# Periph.net
KiCad netlist of a schematic drawn in Altium Designer
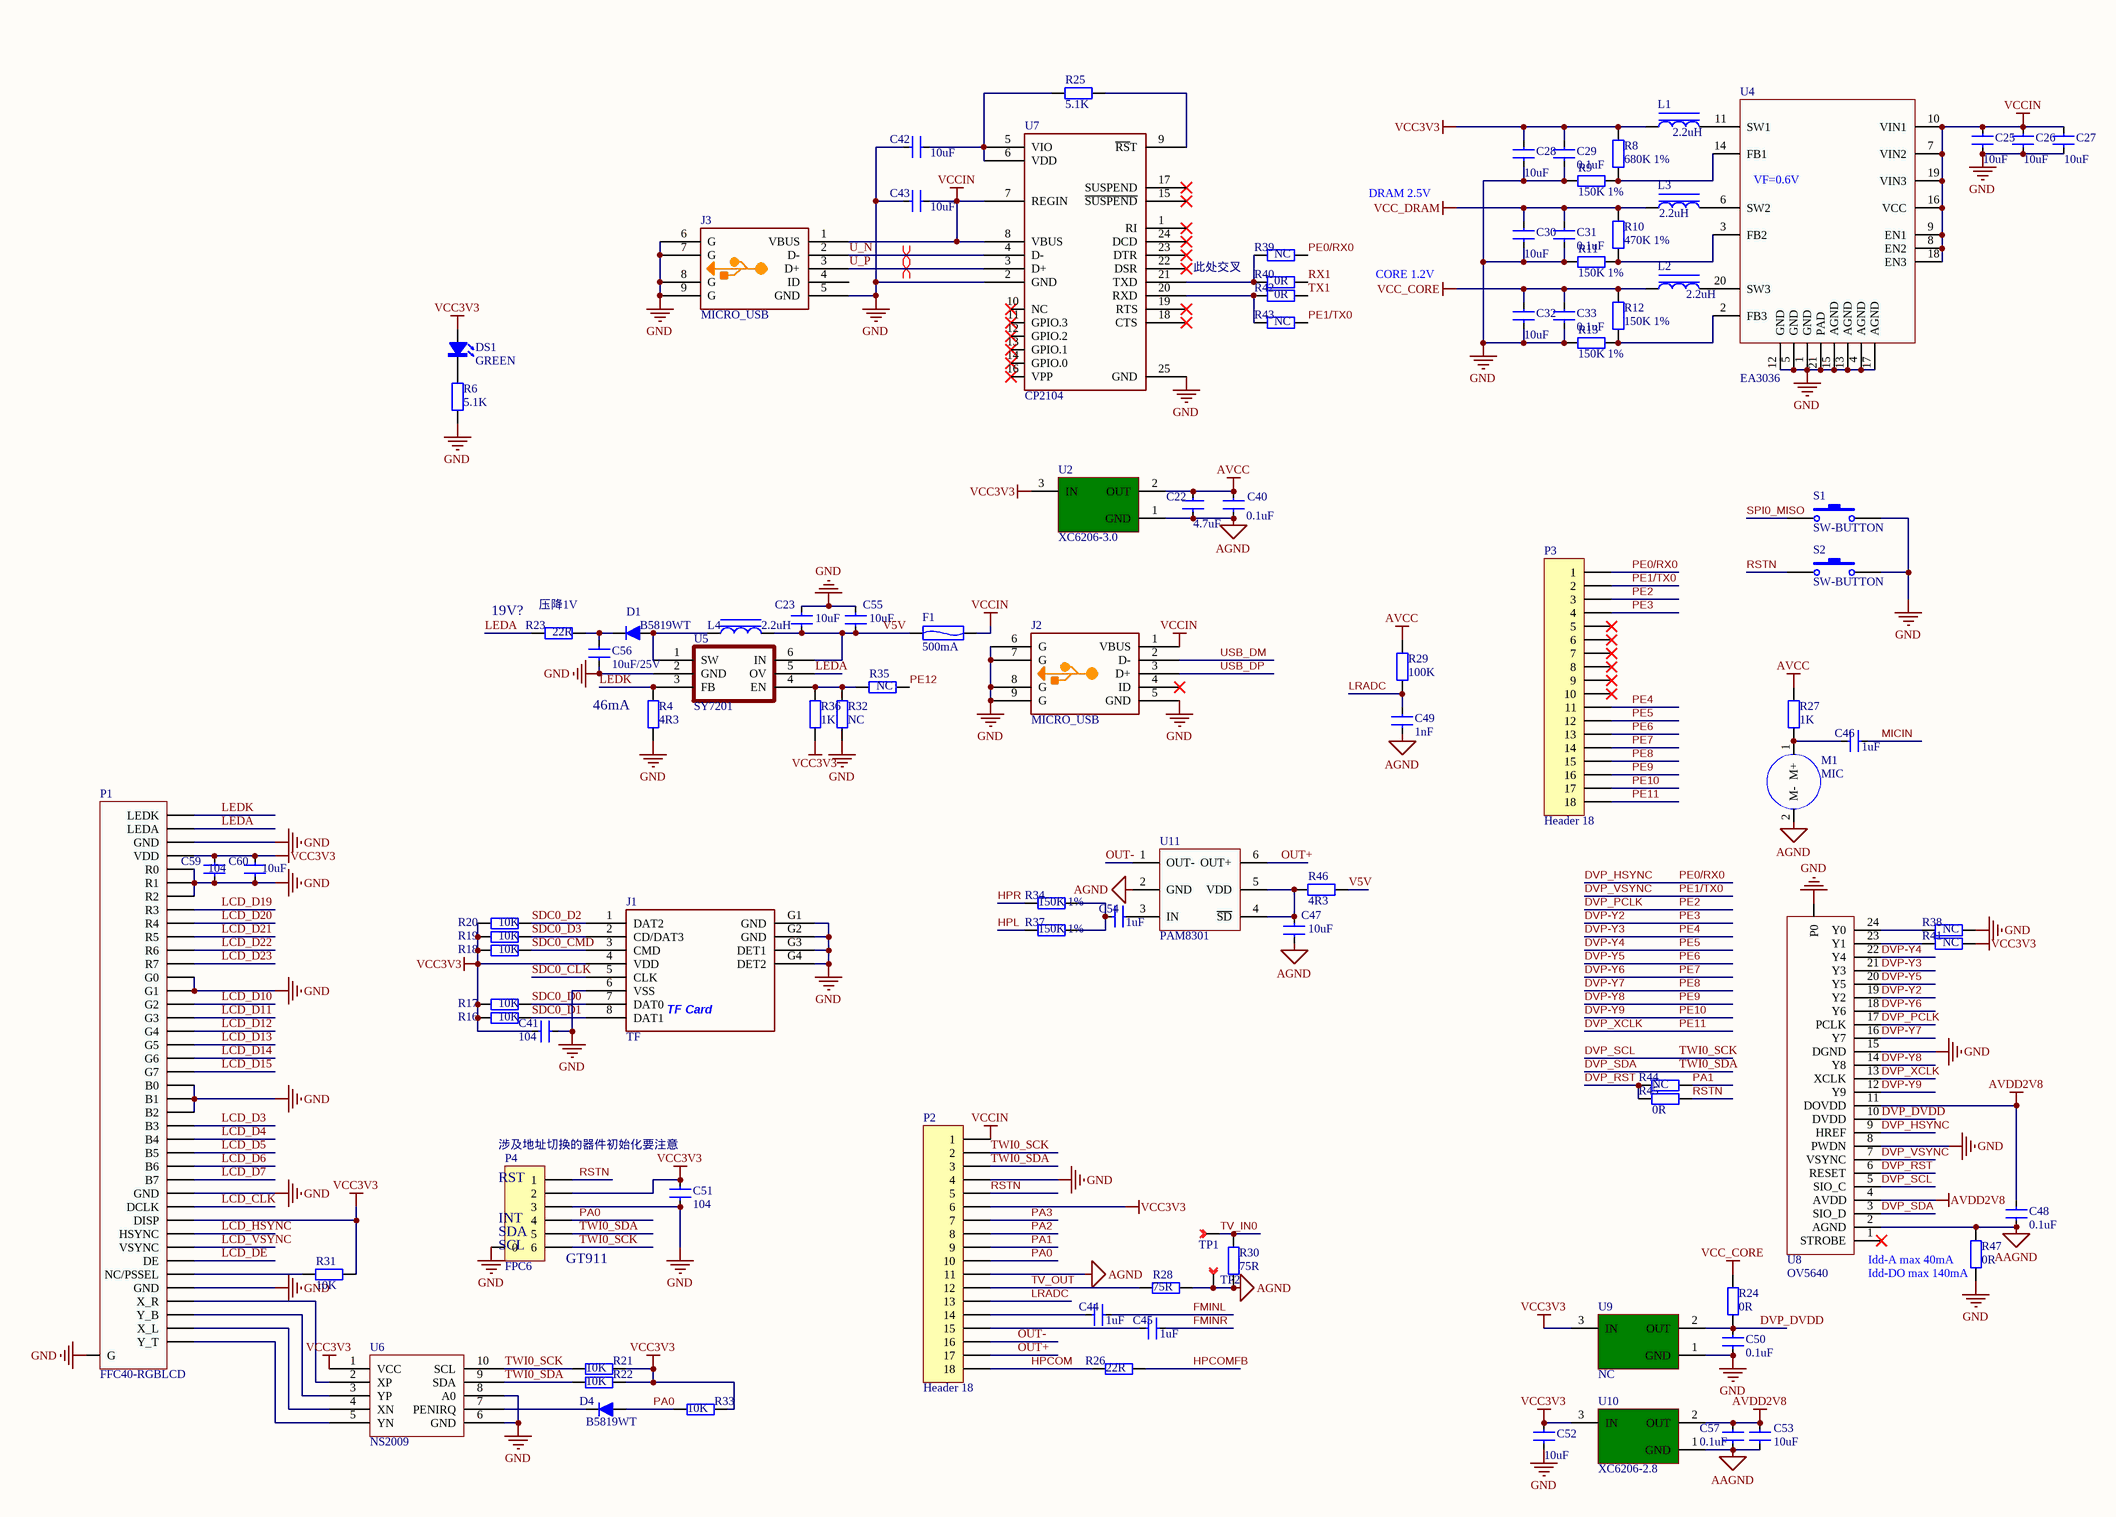
[diagram p0: Periph.SchDoc]

(export (version "E")
  (design (tool "Eeschema 10.0.6"))
  (components
    (comp (ref "C22")
      (value "4.7uF")
      (footprint "C0402")
      (description "普通小电容")
      (libsource (lib "LIB_MANGO") (part "CAP"))
    )
    (comp (ref "C23")
      (value "10uF")
      (footprint "C0402")
      (description "普通小电容")
      (libsource (lib "LIB_MANGO") (part "CAP"))
    )
    (comp (ref "C25")
      (value "10uF")
      (footprint "C0402")
      (description "普通小电容")
      (libsource (lib "LIB_MANGO") (part "CAP"))
    )
    (comp (ref "C26")
      (value "10uF")
      (footprint "C0402")
      (description "普通小电容")
      (libsource (lib "LIB_MANGO") (part "CAP"))
    )
    (comp (ref "C27")
      (value "10uF")
      (footprint "C0402")
      (description "普通小电容")
      (libsource (lib "LIB_MANGO") (part "CAP"))
    )
    (comp (ref "C28")
      (value "10uF")
      (footprint "C0402")
      (description "普通小电容")
      (libsource (lib "LIB_MANGO") (part "CAP"))
    )
    (comp (ref "C29")
      (value "0.1uF")
      (footprint "C0402")
      (description "普通小电容")
      (libsource (lib "LIB_MANGO") (part "CAP"))
    )
    (comp (ref "C30")
      (value "10uF")
      (footprint "C0402")
      (description "普通小电容")
      (libsource (lib "LIB_MANGO") (part "CAP"))
    )
    (comp (ref "C31")
      (value "0.1uF")
      (footprint "C0402")
      (description "普通小电容")
      (libsource (lib "LIB_MANGO") (part "CAP"))
    )
    (comp (ref "C32")
      (value "10uF")
      (footprint "C0402")
      (description "普通小电容")
      (libsource (lib "LIB_MANGO") (part "CAP"))
    )
    (comp (ref "C33")
      (value "0.1uF")
      (footprint "C0402")
      (description "普通小电容")
      (libsource (lib "LIB_MANGO") (part "CAP"))
    )
    (comp (ref "C40")
      (value "0.1uF")
      (footprint "C0402")
      (description "普通小电容")
      (libsource (lib "LIB_MANGO") (part "CAP"))
    )
    (comp (ref "C41")
      (value "104")
      (footprint "C0402")
      (description "普通小电容")
      (libsource (lib "LIB_MANGO") (part "CAP"))
    )
    (comp (ref "C42")
      (value "10uF")
      (footprint "C0402")
      (description "普通小电容")
      (libsource (lib "LIB_MANGO") (part "CAP"))
    )
    (comp (ref "C43")
      (value "10uF")
      (footprint "C0402")
      (description "普通小电容")
      (libsource (lib "LIB_MANGO") (part "CAP"))
    )
    (comp (ref "C44")
      (value "1uF")
      (footprint "C0402")
      (description "普通小电容")
      (libsource (lib "LIB_MANGO") (part "CAP"))
    )
    (comp (ref "C45")
      (value "1uF")
      (footprint "C0402")
      (description "普通小电容")
      (libsource (lib "LIB_MANGO") (part "CAP"))
    )
    (comp (ref "C46")
      (value "1uF")
      (footprint "C0402")
      (description "普通小电容")
      (libsource (lib "LIB_MANGO") (part "CAP"))
    )
    (comp (ref "C47")
      (value "10uF")
      (footprint "C0402")
      (description "普通小电容")
      (libsource (lib "LIB_MANGO") (part "CAP"))
    )
    (comp (ref "C48")
      (value "0.1uF")
      (footprint "C0402")
      (description "普通小电容")
      (libsource (lib "LIB_MANGO") (part "CAP"))
    )
    (comp (ref "C49")
      (value "1nF")
      (footprint "C0402")
      (description "普通小电容")
      (libsource (lib "LIB_MANGO") (part "CAP"))
    )
    (comp (ref "C50")
      (value "0.1uF")
      (footprint "C0402")
      (description "普通小电容")
      (libsource (lib "LIB_MANGO") (part "CAP"))
    )
    (comp (ref "C51")
      (value "104")
      (footprint "C0402")
      (description "普通小电容")
      (libsource (lib "LIB_MANGO") (part "CAP"))
    )
    (comp (ref "C52")
      (value "10uF")
      (footprint "C0402")
      (description "普通小电容")
      (libsource (lib "LIB_MANGO") (part "CAP"))
    )
    (comp (ref "C53")
      (value "10uF")
      (footprint "C0402")
      (description "普通小电容")
      (libsource (lib "LIB_MANGO") (part "CAP"))
    )
    (comp (ref "C54")
      (value "1uF")
      (footprint "C0402")
      (description "普通小电容")
      (libsource (lib "LIB_MANGO") (part "CAP"))
    )
    (comp (ref "C55")
      (value "10uF")
      (footprint "C0402")
      (description "普通小电容")
      (libsource (lib "LIB_MANGO") (part "CAP"))
    )
    (comp (ref "C56")
      (value "10uF/25V")
      (footprint "C0603")
      (description "普通小电容")
      (libsource (lib "LIB_MANGO") (part "CAP"))
    )
    (comp (ref "C57")
      (value "0.1uF")
      (footprint "C0402")
      (description "普通小电容")
      (libsource (lib "LIB_MANGO") (part "CAP"))
    )
    (comp (ref "C59")
      (value "104")
      (footprint "C0402")
      (description "普通小电容")
      (libsource (lib "LIB_MANGO") (part "CAP"))
    )
    (comp (ref "C60")
      (value "10uF")
      (footprint "C0402")
      (description "普通小电容")
      (libsource (lib "LIB_MANGO") (part "CAP"))
    )
    (comp (ref "D1")
      (value "B5819WT")
      (footprint "SOD523")
      (description "普通二极管")
      (libsource (lib "A") (part "Diode"))
    )
    (comp (ref "D4")
      (value "B5819WT")
      (footprint "SOD523")
      (description "普通二极管")
      (libsource (lib "A") (part "Diode"))
    )
    (comp (ref "DS1") (value "GREEN") (footprint "LED0402") (libsource (lib "A") (part "LED")))
    (comp (ref "F1") (value "500mA") (footprint "0805F") (libsource (lib "LIB_MANGO") (part "FUSE")))
    (comp (ref "J1")
      (value "TF")
      (footprint "TFCARD473092651")
      (libsource (lib "LIB_MANGO") (part "TF_473092651"))
    )
    (comp (ref "J2")
      (value "MICRO_USB")
      (footprint "MICROUSB-youxin")
      (libsource (lib "A") (part "MICRO_USB"))
    )
    (comp (ref "J3")
      (value "MICRO_USB")
      (footprint "MICROUSB-youxin")
      (libsource (lib "A") (part "MICRO_USB"))
    )
    (comp (ref "L1")
      (value "2.2uH")
      (footprint "VLS2016")
      (description "普通电感")
      (libsource (lib "LIB_MANGO") (part "L"))
    )
    (comp (ref "L2")
      (value "2.2uH")
      (footprint "VLS2016")
      (description "普通电感")
      (libsource (lib "LIB_MANGO") (part "L"))
    )
    (comp (ref "L3")
      (value "2.2uH")
      (footprint "VLS2016")
      (description "普通电感")
      (libsource (lib "A") (part "L"))
    )
    (comp (ref "L4")
      (value "2.2uH")
      (footprint "VLS3012E")
      (description "普通电感")
      (libsource (lib "LIB_MANGO") (part "L"))
    )
    (comp (ref "M1") (value "MIC") (footprint "MIC") (libsource (lib "LIB_MANGO") (part "MIC")))
    (comp (ref "P1")
      (value "FFC40-RGBLCD")
      (footprint "FFC/SM0.5-1H40")
      (fields (field (name "PUBLISHER") "Altium Limited"))
      (libsource (lib "LIB_MANGO") (part "FFC40-RGBLCD"))
    )
    (comp (ref "P2")
      (value "Header 18")
      (footprint "HDR1X18-M2")
      (description "Header, 18-Pin")
      (fields (field (name "PUBLISHER") "Altium Limited"))
      (libsource (lib "LIB_MANGO") (part "Header 18"))
    )
    (comp (ref "P3")
      (value "Header 18")
      (footprint "HDR1X18-M2")
      (description "Header, 18-Pin")
      (fields (field (name "PUBLISHER") "Altium Limited"))
      (libsource (lib "LIB_MANGO") (part "Header 18"))
    )
    (comp (ref "P4")
      (value "FPC6")
      (footprint "FPC6")
      (fields (field (name "PUBLISHER") "Altium Limited"))
      (libsource (lib "LIB_MANGO") (part "FPC6"))
    )
    (comp (ref "R4")
      (value "4R3")
      (footprint "R0402")
      (description "普通电阻")
      (libsource (lib "") (part "RES_1"))
    )
    (comp (ref "R6")
      (value "5.1K")
      (footprint "R0402")
      (description "普通电阻1%精度")
      (libsource (lib "") (part "RES_2"))
    )
    (comp (ref "R8")
      (value "680K 1%")
      (footprint "R0402")
      (description "普通电阻")
      (libsource (lib "") (part "RES_2"))
    )
    (comp (ref "R9")
      (value "150K 1%")
      (footprint "R0402")
      (description "普通电阻")
      (libsource (lib "LIB_MANGO") (part "RES"))
    )
    (comp (ref "R10")
      (value "470K 1%")
      (footprint "R0402")
      (description "普通电阻")
      (libsource (lib "") (part "RES_2"))
    )
    (comp (ref "R11")
      (value "150K 1%")
      (footprint "R0402")
      (description "普通电阻")
      (libsource (lib "LIB_MANGO") (part "RES"))
    )
    (comp (ref "R12")
      (value "150K 1%")
      (footprint "R0402")
      (description "普通电阻")
      (libsource (lib "") (part "RES_2"))
    )
    (comp (ref "R13")
      (value "150K 1%")
      (footprint "R0402")
      (description "普通电阻")
      (libsource (lib "LIB_MANGO") (part "RES"))
    )
    (comp (ref "R16")
      (value "10K")
      (footprint "R0402")
      (description "普通电阻")
      (libsource (lib "") (part "RES_1"))
    )
    (comp (ref "R17")
      (value "10K")
      (footprint "R0402")
      (description "普通电阻")
      (libsource (lib "") (part "RES_1"))
    )
    (comp (ref "R18")
      (value "10K")
      (footprint "R0402")
      (description "普通电阻")
      (libsource (lib "") (part "RES_1"))
    )
    (comp (ref "R19")
      (value "10K")
      (footprint "R0402")
      (description "普通电阻")
      (libsource (lib "") (part "RES_1"))
    )
    (comp (ref "R20")
      (value "10K")
      (footprint "R0402")
      (description "普通电阻")
      (libsource (lib "") (part "RES_1"))
    )
    (comp (ref "R21")
      (value "10K")
      (footprint "R0402")
      (description "普通电阻")
      (libsource (lib "") (part "RES_3"))
    )
    (comp (ref "R22")
      (value "10K")
      (footprint "R0402")
      (description "普通电阻")
      (libsource (lib "") (part "RES_3"))
    )
    (comp (ref "R23")
      (value "22R")
      (footprint "R0603")
      (description "普通电阻")
      (libsource (lib "LIB_MANGO") (part "RES"))
    )
    (comp (ref "R24")
      (value "0R")
      (footprint "R0402")
      (description "普通电阻")
      (libsource (lib "") (part "RES_1"))
    )
    (comp (ref "R25")
      (value "5.1K")
      (footprint "R0402")
      (description "普通电阻")
      (libsource (lib "") (part "RES_3"))
    )
    (comp (ref "R26")
      (value "22R")
      (footprint "R0402")
      (description "普通电阻")
      (libsource (lib "") (part "RES_3"))
    )
    (comp (ref "R27")
      (value "1K")
      (footprint "R0402")
      (description "普通电阻")
      (libsource (lib "") (part "RES_2"))
    )
    (comp (ref "R28")
      (value "75R")
      (footprint "R0402")
      (description "普通电阻")
      (libsource (lib "") (part "RES_3"))
    )
    (comp (ref "R29")
      (value "100K")
      (footprint "R0402")
      (description "普通电阻")
      (libsource (lib "") (part "RES_1"))
    )
    (comp (ref "R30")
      (value "75R")
      (footprint "R0402")
      (description "普通电阻")
      (libsource (lib "") (part "RES_2"))
    )
    (comp (ref "R31")
      (value "10K")
      (footprint "R0402")
      (description "普通电阻")
      (libsource (lib "LIB_MANGO") (part "RES"))
    )
    (comp (ref "R32")
      (value "NC")
      (footprint "R0402")
      (description "普通电阻")
      (libsource (lib "") (part "RES_2"))
    )
    (comp (ref "R33")
      (value "10K")
      (footprint "R0402")
      (description "普通电阻")
      (libsource (lib "") (part "RES_3"))
    )
    (comp (ref "R34")
      (value "150K 1%")
      (footprint "R0402")
      (description "普通电阻")
      (libsource (lib "LIB_MANGO") (part "RES"))
    )
    (comp (ref "R35")
      (value "NC")
      (footprint "R0402")
      (description "普通电阻")
      (libsource (lib "") (part "RES_3"))
    )
    (comp (ref "R36")
      (value "1K")
      (footprint "R0402")
      (description "普通电阻")
      (libsource (lib "") (part "RES_1"))
    )
    (comp (ref "R37")
      (value "150K 1%")
      (footprint "R0402")
      (description "普通电阻")
      (libsource (lib "LIB_MANGO") (part "RES"))
    )
    (comp (ref "R38")
      (value "NC")
      (footprint "R0402")
      (description "普通电阻")
      (libsource (lib "") (part "RES_3"))
    )
    (comp (ref "R39")
      (value "NC")
      (footprint "R0402")
      (description "普通电阻")
      (libsource (lib "LIB_MANGO") (part "RES"))
    )
    (comp (ref "R40")
      (value "0R")
      (footprint "R0402")
      (description "普通电阻")
      (libsource (lib "LIB_MANGO") (part "RES"))
    )
    (comp (ref "R41")
      (value "NC")
      (footprint "R0402")
      (description "普通电阻")
      (libsource (lib "") (part "RES_3"))
    )
    (comp (ref "R42")
      (value "0R")
      (footprint "R0402")
      (description "普通电阻")
      (libsource (lib "LIB_MANGO") (part "RES"))
    )
    (comp (ref "R43")
      (value "NC")
      (footprint "R0402")
      (description "普通电阻")
      (libsource (lib "LIB_MANGO") (part "RES"))
    )
    (comp (ref "R44")
      (value "NC")
      (footprint "R0402")
      (description "普通电阻")
      (libsource (lib "LIB_MANGO") (part "RES"))
    )
    (comp (ref "R45")
      (value "0R")
      (footprint "R0402")
      (description "普通电阻")
      (libsource (lib "") (part "RES_3"))
    )
    (comp (ref "R46")
      (value "4R3")
      (footprint "R0402")
      (description "普通电阻")
      (libsource (lib "LIB_MANGO") (part "RES"))
    )
    (comp (ref "R47")
      (value "0R")
      (footprint "R0402")
      (description "普通电阻")
      (libsource (lib "") (part "RES_2"))
    )
    (comp (ref "S1")
      (value "SW-BUTTON")
      (footprint "MINIBUTTON")
      (libsource (lib "LIB_MANGO") (part "SW-BUTTON"))
    )
    (comp (ref "S2")
      (value "SW-BUTTON")
      (footprint "MINIBUTTON")
      (libsource (lib "LIB_MANGO") (part "SW-BUTTON"))
    )
    (comp (ref "TP1")
      (value "TEST POINT")
      (footprint "TEST-POINT")
      (description "Description")
      (libsource (lib "LIB_MANGO") (part "TP"))
    )
    (comp (ref "TP2")
      (value "TEST POINT")
      (footprint "TEST-POINT")
      (description "Description")
      (libsource (lib "LIB_MANGO") (part "TP"))
    )
    (comp (ref "U2") (value "XC6206-3.0") (footprint "SOT23") (libsource (lib "LIB_MANGO") (part "XC6206")))
    (comp (ref "U4")
      (value "EA3036")
      (footprint "QFN40P300X300X80_HS-21N")
      (libsource (lib "LIB_MANGO") (part "EA3036"))
    )
    (comp (ref "U5") (value "SY7201") (footprint "SOT23-6") (libsource (lib "LIB_MANGO") (part "PT4101")))
    (comp (ref "U6") (value "NS2009") (footprint "TSSOP10") (libsource (lib "LIB_MANGO") (part "NS2009")))
    (comp (ref "U7") (value "CP2104") (footprint "QFN24") (libsource (lib "LIB_MANGO") (part "CP2104")))
    (comp (ref "U8")
      (value "OV5640")
      (footprint "FFC/SM0.5-1H24 - OV2640")
      (description "Header, 24-Pin")
      (fields (field (name "PUBLISHER") "Altium Limited"))
      (libsource (lib "A") (part "OV5640"))
    )
    (comp (ref "U9") (value "NC") (footprint "SOT23") (libsource (lib "LIB_MANGO") (part "XC6206")))
    (comp (ref "U10") (value "XC6206-2.8") (footprint "SOT23") (libsource (lib "LIB_MANGO") (part "XC6206")))
    (comp (ref "U11") (value "PAM8301") (footprint "SOT23-6") (libsource (lib "LIB_MANGO") (part "PAM8301")))
  )
  (nets
    (net (code "1") (name "/DVP-Y2") (class "Default")
      (node (ref "P3") (pin "4") (pinfunction "4_4") (pintype "passive"))
      (node (ref "U8") (pin "19") (pinfunction "Y2_19") (pintype "passive"))
    )
    (net (code "2") (name "/DVP-Y3") (class "Default")
      (node (ref "P3") (pin "11") (pinfunction "11_11") (pintype "passive"))
      (node (ref "U8") (pin "21") (pinfunction "Y3_21") (pintype "passive"))
    )
    (net (code "3") (name "/DVP-Y4") (class "Default")
      (node (ref "P3") (pin "12") (pinfunction "12_12") (pintype "passive"))
      (node (ref "U8") (pin "22") (pinfunction "Y4_22") (pintype "passive"))
    )
    (net (code "4") (name "/DVP-Y5") (class "Default")
      (node (ref "P3") (pin "13") (pinfunction "13_13") (pintype "passive"))
      (node (ref "U8") (pin "20") (pinfunction "Y5_20") (pintype "passive"))
    )
    (net (code "5") (name "/DVP-Y6") (class "Default")
      (node (ref "P3") (pin "14") (pinfunction "14_14") (pintype "passive"))
      (node (ref "U8") (pin "18") (pinfunction "Y6_18") (pintype "passive"))
    )
    (net (code "6") (name "/DVP-Y7") (class "Default")
      (node (ref "P3") (pin "15") (pinfunction "15_15") (pintype "passive"))
      (node (ref "U8") (pin "16") (pinfunction "Y7_16") (pintype "passive"))
    )
    (net (code "7") (name "/DVP-Y8") (class "Default")
      (node (ref "P3") (pin "16") (pinfunction "16_16") (pintype "passive"))
      (node (ref "U8") (pin "14") (pinfunction "Y8_14") (pintype "passive"))
    )
    (net (code "8") (name "/DVP-Y9") (class "Default")
      (node (ref "P3") (pin "17") (pinfunction "17_17") (pintype "passive"))
      (node (ref "U8") (pin "12") (pinfunction "Y9_12") (pintype "passive"))
    )
    (net (code "9") (name "/DVP_DVDD") (class "Default")
      (node (ref "C50") (pin "2") (pinfunction "2_2") (pintype "passive"))
      (node (ref "R24") (pin "1") (pinfunction "1_1") (pintype "passive"))
      (node (ref "U8") (pin "10") (pinfunction "DVDD_10") (pintype "passive"))
      (node (ref "U9") (pin "2") (pinfunction "OUT_2") (pintype "passive"))
    )
    (net (code "10") (name "/DVP_HSYNC") (class "Default")
      (node (ref "P3") (pin "1") (pinfunction "1_1") (pintype "passive"))
      (node (ref "R39") (pin "1") (pinfunction "1_1") (pintype "passive"))
      (node (ref "U8") (pin "9") (pinfunction "HREF_9") (pintype "passive"))
    )
    (net (code "11") (name "/DVP_PCLK") (class "Default")
      (node (ref "P3") (pin "3") (pinfunction "3_3") (pintype "passive"))
      (node (ref "U8") (pin "17") (pinfunction "PCLK_17") (pintype "passive"))
    )
    (net (code "12") (name "/DVP_RST") (class "Default")
      (node (ref "R44") (pin "2") (pinfunction "2_2") (pintype "passive"))
      (node (ref "R45") (pin "1") (pinfunction "1_1") (pintype "passive"))
      (node (ref "U8") (pin "6") (pinfunction "RESET_6") (pintype "passive"))
    )
    (net (code "13") (name "/DVP_SCL") (class "Default")
      (node (ref "P2") (pin "2") (pinfunction "2_2") (pintype "passive"))
      (node (ref "P4") (pin "6") (pinfunction "6_6") (pintype "passive"))
      (node (ref "R21") (pin "1") (pinfunction "1_1") (pintype "passive"))
      (node (ref "U6") (pin "10") (pinfunction "SCL_10") (pintype "passive"))
      (node (ref "U8") (pin "5") (pinfunction "SIO_C_5") (pintype "passive"))
    )
    (net (code "14") (name "/DVP_SDA") (class "Default")
      (node (ref "P2") (pin "3") (pinfunction "3_3") (pintype "passive"))
      (node (ref "P4") (pin "5") (pinfunction "5_5") (pintype "passive"))
      (node (ref "R22") (pin "1") (pinfunction "1_1") (pintype "passive"))
      (node (ref "U6") (pin "9") (pinfunction "SDA_9") (pintype "passive"))
      (node (ref "U8") (pin "3") (pinfunction "SIO_D_3") (pintype "passive"))
    )
    (net (code "15") (name "/DVP_VSYNC") (class "Default")
      (node (ref "P3") (pin "2") (pinfunction "2_2") (pintype "passive"))
      (node (ref "R43") (pin "1") (pinfunction "1_1") (pintype "passive"))
      (node (ref "U8") (pin "7") (pinfunction "VSYNC_7") (pintype "passive"))
    )
    (net (code "16") (name "/DVP_XCLK") (class "Default")
      (node (ref "P3") (pin "18") (pinfunction "18_18") (pintype "passive"))
      (node (ref "U8") (pin "13") (pinfunction "XCLK_13") (pintype "passive"))
    )
    (net (code "17") (name "/FMINL") (class "Default")
      (node (ref "C44") (pin "2") (pinfunction "2_2") (pintype "passive"))
    )
    (net (code "18") (name "/FMINR") (class "Default")
      (node (ref "C45") (pin "2") (pinfunction "2_2") (pintype "passive"))
    )
    (net (code "19") (name "/HPCOM") (class "Default")
      (node (ref "P2") (pin "18") (pinfunction "18_18") (pintype "passive"))
      (node (ref "R26") (pin "1") (pinfunction "1_1") (pintype "passive"))
    )
    (net (code "20") (name "/HPCOMFB") (class "Default")
      (node (ref "R26") (pin "2") (pinfunction "2_2") (pintype "passive"))
    )
    (net (code "21") (name "/HPL") (class "Default")
      (node (ref "R37") (pin "2") (pinfunction "2_2") (pintype "passive"))
    )
    (net (code "22") (name "/HPR") (class "Default")
      (node (ref "R34") (pin "2") (pinfunction "2_2") (pintype "passive"))
    )
    (net (code "23") (name "/LCD_CLK") (class "Default")
      (node (ref "P1") (pin "30") (pinfunction "DCLK_30") (pintype "passive"))
    )
    (net (code "24") (name "/LCD_D3") (class "Default")
      (node (ref "P1") (pin "24") (pinfunction "B3_24") (pintype "passive"))
    )
    (net (code "25") (name "/LCD_D4") (class "Default")
      (node (ref "P1") (pin "25") (pinfunction "B4_25") (pintype "passive"))
    )
    (net (code "26") (name "/LCD_D5") (class "Default")
      (node (ref "P1") (pin "26") (pinfunction "B5_26") (pintype "passive"))
    )
    (net (code "27") (name "/LCD_D6") (class "Default")
      (node (ref "P1") (pin "27") (pinfunction "B6_27") (pintype "passive"))
    )
    (net (code "28") (name "/LCD_D7") (class "Default")
      (node (ref "P1") (pin "28") (pinfunction "B7_28") (pintype "passive"))
    )
    (net (code "29") (name "/LCD_D10") (class "Default")
      (node (ref "P1") (pin "15") (pinfunction "G2_15") (pintype "passive"))
    )
    (net (code "30") (name "/LCD_D11") (class "Default")
      (node (ref "P1") (pin "16") (pinfunction "G3_16") (pintype "passive"))
    )
    (net (code "31") (name "/LCD_D12") (class "Default")
      (node (ref "P1") (pin "17") (pinfunction "G4_17") (pintype "passive"))
    )
    (net (code "32") (name "/LCD_D13") (class "Default")
      (node (ref "P1") (pin "18") (pinfunction "G5_18") (pintype "passive"))
    )
    (net (code "33") (name "/LCD_D14") (class "Default")
      (node (ref "P1") (pin "19") (pinfunction "G6_19") (pintype "passive"))
    )
    (net (code "34") (name "/LCD_D15") (class "Default")
      (node (ref "P1") (pin "20") (pinfunction "G7_20") (pintype "passive"))
    )
    (net (code "35") (name "/LCD_D19") (class "Default")
      (node (ref "P1") (pin "8") (pinfunction "R3_8") (pintype "passive"))
    )
    (net (code "36") (name "/LCD_D20") (class "Default")
      (node (ref "P1") (pin "9") (pinfunction "R4_9") (pintype "passive"))
    )
    (net (code "37") (name "/LCD_D21") (class "Default")
      (node (ref "P1") (pin "10") (pinfunction "R5_10") (pintype "passive"))
    )
    (net (code "38") (name "/LCD_D22") (class "Default")
      (node (ref "P1") (pin "11") (pinfunction "R6_11") (pintype "passive"))
    )
    (net (code "39") (name "/LCD_D23") (class "Default")
      (node (ref "P1") (pin "12") (pinfunction "R7_12") (pintype "passive"))
    )
    (net (code "40") (name "/LCD_DE") (class "Default")
      (node (ref "P1") (pin "34") (pinfunction "DE_34") (pintype "passive"))
    )
    (net (code "41") (name "/LCD_HSYNC") (class "Default")
      (node (ref "P1") (pin "32") (pinfunction "HSYNC_32") (pintype "passive"))
    )
    (net (code "42") (name "/LCD_VSYNC") (class "Default")
      (node (ref "P1") (pin "33") (pinfunction "VSYNC_33") (pintype "passive"))
    )
    (net (code "43") (name "/LEDA") (class "Default")
      (node (ref "P1") (pin "2") (pinfunction "LEDA_2") (pintype "passive"))
      (node (ref "R23") (pin "2") (pinfunction "2_2") (pintype "passive"))
      (node (ref "U5") (pin "5") (pinfunction "OV_5") (pintype "passive"))
    )
    (net (code "44") (name "/LEDK") (class "Default")
      (node (ref "P1") (pin "1") (pinfunction "LEDK_1") (pintype "passive"))
      (node (ref "R4") (pin "2") (pinfunction "2_2") (pintype "passive"))
      (node (ref "U5") (pin "3") (pinfunction "FB_3") (pintype "passive"))
    )
    (net (code "45") (name "/LRADC") (class "Default")
      (node (ref "C49") (pin "2") (pinfunction "2_2") (pintype "passive"))
      (node (ref "P2") (pin "13") (pinfunction "13_13") (pintype "passive"))
      (node (ref "R29") (pin "1") (pinfunction "1_1") (pintype "passive"))
    )
    (net (code "46") (name "/MICIN") (class "Default")
      (node (ref "C46") (pin "2") (pinfunction "2_2") (pintype "passive"))
    )
    (net (code "47") (name "/OUT+") (class "Default")
      (node (ref "P2") (pin "17") (pinfunction "17_17") (pintype "passive"))
      (node (ref "U11") (pin "6") (pinfunction "OUT+_6") (pintype "passive"))
    )
    (net (code "48") (name "/OUT-") (class "Default")
      (node (ref "P2") (pin "16") (pinfunction "16_16") (pintype "passive"))
      (node (ref "U11") (pin "1") (pinfunction "OUT-_1") (pintype "passive"))
    )
    (net (code "49") (name "/PA0") (class "Default")
      (node (ref "D4") (pin "A") (pinfunction "A_A") (pintype "passive"))
      (node (ref "P2") (pin "10") (pinfunction "10_10") (pintype "passive"))
      (node (ref "P4") (pin "4") (pinfunction "4_4") (pintype "passive"))
      (node (ref "R33") (pin "1") (pinfunction "1_1") (pintype "passive"))
    )
    (net (code "50") (name "/PA1") (class "Default")
      (node (ref "P2") (pin "9") (pinfunction "9_9") (pintype "passive"))
      (node (ref "R44") (pin "1") (pinfunction "1_1") (pintype "passive"))
    )
    (net (code "51") (name "/PA2") (class "Default")
      (node (ref "P2") (pin "8") (pinfunction "8_8") (pintype "passive"))
    )
    (net (code "52") (name "/PA3") (class "Default")
      (node (ref "P2") (pin "7") (pinfunction "7_7") (pintype "passive"))
    )
    (net (code "53") (name "/PE12") (class "Default")
      (node (ref "R35") (pin "2") (pinfunction "2_2") (pintype "passive"))
    )
    (net (code "54") (name "/RSTN") (class "Default")
      (node (ref "P2") (pin "5") (pinfunction "5_5") (pintype "passive"))
      (node (ref "P4") (pin "1") (pinfunction "1_1") (pintype "passive"))
      (node (ref "R45") (pin "2") (pinfunction "2_2") (pintype "passive"))
      (node (ref "S2") (pin "1") (pinfunction "1_1") (pintype "passive"))
    )
    (net (code "55") (name "/RX1") (class "Default")
      (node (ref "R40") (pin "1") (pinfunction "1_1") (pintype "passive"))
    )
    (net (code "56") (name "/SDC0_CLK") (class "Default")
      (node (ref "J1") (pin "5") (pinfunction "CLK_5") (pintype "passive"))
    )
    (net (code "57") (name "/SDC0_CMD") (class "Default")
      (node (ref "J1") (pin "3") (pinfunction "CMD_3") (pintype "passive"))
      (node (ref "R18") (pin "2") (pinfunction "2_2") (pintype "passive"))
    )
    (net (code "58") (name "/SDC0_D0") (class "Default")
      (node (ref "J1") (pin "7") (pinfunction "DAT0_7") (pintype "passive"))
      (node (ref "R17") (pin "2") (pinfunction "2_2") (pintype "passive"))
    )
    (net (code "59") (name "/SDC0_D1") (class "Default")
      (node (ref "J1") (pin "8") (pinfunction "DAT1_8") (pintype "passive"))
      (node (ref "R16") (pin "2") (pinfunction "2_2") (pintype "passive"))
    )
    (net (code "60") (name "/SDC0_D2") (class "Default")
      (node (ref "J1") (pin "1") (pinfunction "DAT2_1") (pintype "passive"))
      (node (ref "R20") (pin "2") (pinfunction "2_2") (pintype "passive"))
    )
    (net (code "61") (name "/SDC0_D3") (class "Default")
      (node (ref "J1") (pin "2") (pinfunction "CD/DAT3_2") (pintype "passive"))
      (node (ref "R19") (pin "2") (pinfunction "2_2") (pintype "passive"))
    )
    (net (code "62") (name "/SPI0_MISO") (class "Default")
      (node (ref "S1") (pin "1") (pinfunction "1_1") (pintype "passive"))
    )
    (net (code "63") (name "/TV_IN0") (class "Default")
      (node (ref "R30") (pin "1") (pinfunction "1_1") (pintype "passive"))
      (node (ref "TP1") (pin "1") (pinfunction "1_1") (pintype "passive"))
    )
    (net (code "64") (name "/TV_OUT") (class "Default")
      (node (ref "P2") (pin "12") (pinfunction "12_12") (pintype "passive"))
      (node (ref "R28") (pin "1") (pinfunction "1_1") (pintype "passive"))
    )
    (net (code "65") (name "/TX1") (class "Default")
      (node (ref "R42") (pin "1") (pinfunction "1_1") (pintype "passive"))
    )
    (net (code "66") (name "/USB_DM") (class "Default")
      (node (ref "J2") (pin "2") (pinfunction "D-_2") (pintype "passive"))
    )
    (net (code "67") (name "/USB_DP") (class "Default")
      (node (ref "J2") (pin "3") (pinfunction "D+_3") (pintype "passive"))
    )
    (net (code "68") (name "/U_N") (class "Default")
      (node (ref "J3") (pin "2") (pinfunction "D-_2") (pintype "passive"))
      (node (ref "U7") (pin "4") (pinfunction "D-_4") (pintype "passive"))
    )
    (net (code "69") (name "/U_P") (class "Default")
      (node (ref "J3") (pin "3") (pinfunction "D+_3") (pintype "passive"))
      (node (ref "U7") (pin "3") (pinfunction "D+_3") (pintype "passive"))
    )
    (net (code "70") (name "/V5V") (class "Default")
      (node (ref "C23") (pin "1") (pinfunction "1_1") (pintype "passive"))
      (node (ref "C55") (pin "2") (pinfunction "2_2") (pintype "passive"))
      (node (ref "F1") (pin "1") (pinfunction "1_1") (pintype "passive"))
      (node (ref "L4") (pin "1") (pinfunction "1_1") (pintype "passive"))
      (node (ref "R46") (pin "1") (pinfunction "1_1") (pintype "passive"))
      (node (ref "U5") (pin "6") (pinfunction "IN_6") (pintype "passive"))
    )
    (net (code "71") (name "AAGND") (class "Default")
      (node (ref "C48") (pin "1") (pinfunction "1_1") (pintype "passive"))
      (node (ref "C53") (pin "2") (pinfunction "2_2") (pintype "passive"))
      (node (ref "C57") (pin "1") (pinfunction "1_1") (pintype "passive"))
      (node (ref "R47") (pin "1") (pinfunction "1_1") (pintype "passive"))
      (node (ref "U10") (pin "1") (pinfunction "GND_1") (pintype "passive"))
      (node (ref "U8") (pin "2") (pinfunction "AGND_2") (pintype "passive"))
    )
    (net (code "72") (name "AGND") (class "Default")
      (node (ref "C22") (pin "1") (pinfunction "1_1") (pintype "passive"))
      (node (ref "C40") (pin "1") (pinfunction "1_1") (pintype "passive"))
      (node (ref "C47") (pin "2") (pinfunction "2_2") (pintype "passive"))
      (node (ref "C49") (pin "1") (pinfunction "1_1") (pintype "passive"))
      (node (ref "M1") (pin "2") (pinfunction "M-_2") (pintype "passive"))
      (node (ref "P2") (pin "11") (pinfunction "11_11") (pintype "passive"))
      (node (ref "R28") (pin "2") (pinfunction "2_2") (pintype "passive"))
      (node (ref "R30") (pin "2") (pinfunction "2_2") (pintype "passive"))
      (node (ref "TP2") (pin "1") (pinfunction "1_1") (pintype "passive"))
      (node (ref "U11") (pin "2") (pinfunction "GND_2") (pintype "passive"))
      (node (ref "U2") (pin "1") (pinfunction "GND_1") (pintype "passive"))
    )
    (net (code "73") (name "AVCC") (class "Default")
      (node (ref "C22") (pin "2") (pinfunction "2_2") (pintype "passive"))
      (node (ref "C40") (pin "2") (pinfunction "2_2") (pintype "passive"))
      (node (ref "R27") (pin "1") (pinfunction "1_1") (pintype "passive"))
      (node (ref "R29") (pin "2") (pinfunction "2_2") (pintype "passive"))
      (node (ref "U2") (pin "2") (pinfunction "OUT_2") (pintype "passive"))
    )
    (net (code "74") (name "AVDD2V8") (class "Default")
      (node (ref "C48") (pin "2") (pinfunction "2_2") (pintype "passive"))
      (node (ref "C53") (pin "1") (pinfunction "1_1") (pintype "passive"))
      (node (ref "C57") (pin "2") (pinfunction "2_2") (pintype "passive"))
      (node (ref "U10") (pin "2") (pinfunction "OUT_2") (pintype "passive"))
      (node (ref "U8") (pin "11") (pinfunction "DOVDD_11") (pintype "passive"))
      (node (ref "U8") (pin "4") (pinfunction "AVDD_4") (pintype "passive"))
    )
    (net (code "75") (name "GND") (class "Default")
      (node (ref "C23") (pin "2") (pinfunction "2_2") (pintype "passive"))
      (node (ref "C25") (pin "2") (pinfunction "2_2") (pintype "passive"))
      (node (ref "C26") (pin "2") (pinfunction "2_2") (pintype "passive"))
      (node (ref "C27") (pin "2") (pinfunction "2_2") (pintype "passive"))
      (node (ref "C28") (pin "2") (pinfunction "2_2") (pintype "passive"))
      (node (ref "C29") (pin "1") (pinfunction "1_1") (pintype "passive"))
      (node (ref "C30") (pin "2") (pinfunction "2_2") (pintype "passive"))
      (node (ref "C31") (pin "1") (pinfunction "1_1") (pintype "passive"))
      (node (ref "C32") (pin "2") (pinfunction "2_2") (pintype "passive"))
      (node (ref "C33") (pin "1") (pinfunction "1_1") (pintype "passive"))
      (node (ref "C41") (pin "2") (pinfunction "2_2") (pintype "passive"))
      (node (ref "C42") (pin "2") (pinfunction "2_2") (pintype "passive"))
      (node (ref "C43") (pin "1") (pinfunction "1_1") (pintype "passive"))
      (node (ref "C50") (pin "1") (pinfunction "1_1") (pintype "passive"))
      (node (ref "C51") (pin "1") (pinfunction "1_1") (pintype "passive"))
      (node (ref "C52") (pin "2") (pinfunction "2_2") (pintype "passive"))
      (node (ref "C55") (pin "1") (pinfunction "1_1") (pintype "passive"))
      (node (ref "C56") (pin "1") (pinfunction "1_1") (pintype "passive"))
      (node (ref "C59") (pin "2") (pinfunction "2_2") (pintype "passive"))
      (node (ref "C60") (pin "1") (pinfunction "1_1") (pintype "passive"))
      (node (ref "J1") (pin "6") (pinfunction "VSS_6") (pintype "power_in"))
      (node (ref "J1") (pin "G1") (pinfunction "GND_G1") (pintype "power_in"))
      (node (ref "J1") (pin "G2") (pinfunction "GND_G2") (pintype "power_in"))
      (node (ref "J1") (pin "G3") (pinfunction "DET1_G3") (pintype "power_in"))
      (node (ref "J1") (pin "G4") (pinfunction "DET2_G4") (pintype "power_in"))
      (node (ref "J2") (pin "5") (pinfunction "GND_5") (pintype "power_in"))
      (node (ref "J2") (pin "6") (pinfunction "G_6") (pintype "passive"))
      (node (ref "J2") (pin "7") (pinfunction "G_7") (pintype "passive"))
      (node (ref "J2") (pin "8") (pinfunction "G_8") (pintype "passive"))
      (node (ref "J2") (pin "9") (pinfunction "G_9") (pintype "passive"))
      (node (ref "J3") (pin "5") (pinfunction "GND_5") (pintype "power_in"))
      (node (ref "J3") (pin "6") (pinfunction "G_6") (pintype "passive"))
      (node (ref "J3") (pin "7") (pinfunction "G_7") (pintype "passive"))
      (node (ref "J3") (pin "8") (pinfunction "G_8") (pintype "passive"))
      (node (ref "J3") (pin "9") (pinfunction "G_9") (pintype "passive"))
      (node (ref "P1") (pin "13") (pinfunction "G0_13") (pintype "passive"))
      (node (ref "P1") (pin "14") (pinfunction "G1_14") (pintype "passive"))
      (node (ref "P1") (pin "21") (pinfunction "B0_21") (pintype "passive"))
      (node (ref "P1") (pin "22") (pinfunction "B1_22") (pintype "passive"))
      (node (ref "P1") (pin "23") (pinfunction "B2_23") (pintype "passive"))
      (node (ref "P1") (pin "29") (pinfunction "GND_29") (pintype "passive"))
      (node (ref "P1") (pin "3") (pinfunction "GND_3") (pintype "passive"))
      (node (ref "P1") (pin "36") (pinfunction "GND_36") (pintype "passive"))
      (node (ref "P1") (pin "5") (pinfunction "R0_5") (pintype "passive"))
      (node (ref "P1") (pin "6") (pinfunction "R1_6") (pintype "passive"))
      (node (ref "P1") (pin "7") (pinfunction "R2_7") (pintype "passive"))
      (node (ref "P1") (pin "G") (pinfunction "G_G") (pintype "passive"))
      (node (ref "P2") (pin "4") (pinfunction "4_4") (pintype "passive"))
      (node (ref "P4") (pin "0") (pinfunction "0_0") (pintype "passive"))
      (node (ref "P4") (pin "3") (pinfunction "3_3") (pintype "passive"))
      (node (ref "R11") (pin "2") (pinfunction "2_2") (pintype "passive"))
      (node (ref "R13") (pin "2") (pinfunction "2_2") (pintype "passive"))
      (node (ref "R32") (pin "2") (pinfunction "2_2") (pintype "passive"))
      (node (ref "R38") (pin "2") (pinfunction "2_2") (pintype "passive"))
      (node (ref "R4") (pin "1") (pinfunction "1_1") (pintype "passive"))
      (node (ref "R47") (pin "2") (pinfunction "2_2") (pintype "passive"))
      (node (ref "R6") (pin "2") (pinfunction "2_2") (pintype "passive"))
      (node (ref "R9") (pin "2") (pinfunction "2_2") (pintype "passive"))
      (node (ref "S1") (pin "2") (pinfunction "2_2") (pintype "passive"))
      (node (ref "S2") (pin "2") (pinfunction "2_2") (pintype "passive"))
      (node (ref "U4") (pin "1") (pinfunction "GND_1") (pintype "passive"))
      (node (ref "U4") (pin "12") (pinfunction "GND_12") (pintype "passive"))
      (node (ref "U4") (pin "13") (pinfunction "AGND_13") (pintype "passive"))
      (node (ref "U4") (pin "15") (pinfunction "AGND_15") (pintype "passive"))
      (node (ref "U4") (pin "17") (pinfunction "AGND_17") (pintype "passive"))
      (node (ref "U4") (pin "21") (pinfunction "PAD_21") (pintype "passive"))
      (node (ref "U4") (pin "4") (pinfunction "AGND_4") (pintype "passive"))
      (node (ref "U4") (pin "5") (pinfunction "GND_5") (pintype "passive"))
      (node (ref "U5") (pin "2") (pinfunction "GND_2") (pintype "passive"))
      (node (ref "U6") (pin "6") (pinfunction "GND_6") (pintype "passive"))
      (node (ref "U6") (pin "8") (pinfunction "A0_8") (pintype "passive"))
      (node (ref "U7") (pin "2") (pinfunction "GND_2") (pintype "power_in"))
      (node (ref "U7") (pin "25") (pinfunction "GND_25") (pintype "power_in"))
      (node (ref "U8") (pin "15") (pinfunction "DGND_15") (pintype "passive"))
      (node (ref "U8") (pin "8") (pinfunction "PWDN_8") (pintype "passive"))
      (node (ref "U8") (pin "P0") (pinfunction "P0_P0") (pintype "passive"))
      (node (ref "U9") (pin "1") (pinfunction "GND_1") (pintype "passive"))
    )
    (net (code "76") (name "Net-(C44-Pad1)") (class "Default")
      (node (ref "C44") (pin "1") (pinfunction "1_1") (pintype "passive"))
      (node (ref "P2") (pin "14") (pinfunction "14_14") (pintype "passive"))
    )
    (net (code "77") (name "Net-(C45-Pad1)") (class "Default")
      (node (ref "C45") (pin "1") (pinfunction "1_1") (pintype "passive"))
      (node (ref "P2") (pin "15") (pinfunction "15_15") (pintype "passive"))
    )
    (net (code "78") (name "Net-(C54-Pad1)") (class "Default")
      (node (ref "C54") (pin "1") (pinfunction "1_1") (pintype "passive"))
      (node (ref "R34") (pin "1") (pinfunction "1_1") (pintype "passive"))
      (node (ref "R37") (pin "1") (pinfunction "1_1") (pintype "passive"))
    )
    (net (code "79") (name "Net-(C56-Pad2)") (class "Default")
      (node (ref "C56") (pin "2") (pinfunction "2_2") (pintype "passive"))
      (node (ref "D1") (pin "K") (pinfunction "K_K") (pintype "passive"))
      (node (ref "R23") (pin "1") (pinfunction "1_1") (pintype "passive"))
    )
    (net (code "80") (name "Net-(DS1-2)") (class "Default")
      (node (ref "DS1") (pin "K") (pinfunction "2_K") (pintype "passive"))
      (node (ref "R6") (pin "1") (pinfunction "1_1") (pintype "passive"))
    )
    (net (code "81") (name "Net-(M1-M+)") (class "Default")
      (node (ref "C46") (pin "1") (pinfunction "1_1") (pintype "passive"))
      (node (ref "M1") (pin "1") (pinfunction "M+_1") (pintype "passive"))
      (node (ref "R27") (pin "2") (pinfunction "2_2") (pintype "passive"))
    )
    (net (code "82") (name "Net-(P1-NC{slash}PSSEL)") (class "Default")
      (node (ref "P1") (pin "35") (pinfunction "NC/PSSEL_35") (pintype "passive"))
      (node (ref "R31") (pin "2") (pinfunction "2_2") (pintype "passive"))
    )
    (net (code "83") (name "Net-(P1-X_L)") (class "Default")
      (node (ref "P1") (pin "39") (pinfunction "X_L_39") (pintype "passive"))
      (node (ref "U6") (pin "4") (pinfunction "XN_4") (pintype "passive"))
    )
    (net (code "84") (name "Net-(P1-X_R)") (class "Default")
      (node (ref "P1") (pin "37") (pinfunction "X_R_37") (pintype "passive"))
      (node (ref "U6") (pin "2") (pinfunction "XP_2") (pintype "passive"))
    )
    (net (code "85") (name "Net-(P1-Y_B)") (class "Default")
      (node (ref "P1") (pin "38") (pinfunction "Y_B_38") (pintype "passive"))
      (node (ref "U6") (pin "3") (pinfunction "YP_3") (pintype "passive"))
    )
    (net (code "86") (name "Net-(P1-Y_T)") (class "Default")
      (node (ref "P1") (pin "40") (pinfunction "Y_T_40") (pintype "passive"))
      (node (ref "U6") (pin "5") (pinfunction "YN_5") (pintype "passive"))
    )
    (net (code "87") (name "Net-(U4-FB1)") (class "Default")
      (node (ref "R8") (pin "2") (pinfunction "2_2") (pintype "passive"))
      (node (ref "R9") (pin "1") (pinfunction "1_1") (pintype "passive"))
      (node (ref "U4") (pin "14") (pinfunction "FB1_14") (pintype "passive"))
    )
    (net (code "88") (name "Net-(U4-FB2)") (class "Default")
      (node (ref "R10") (pin "2") (pinfunction "2_2") (pintype "passive"))
      (node (ref "R11") (pin "1") (pinfunction "1_1") (pintype "passive"))
      (node (ref "U4") (pin "3") (pinfunction "FB2_3") (pintype "passive"))
    )
    (net (code "89") (name "Net-(U4-FB3)") (class "Default")
      (node (ref "R12") (pin "2") (pinfunction "2_2") (pintype "passive"))
      (node (ref "R13") (pin "1") (pinfunction "1_1") (pintype "passive"))
      (node (ref "U4") (pin "2") (pinfunction "FB3_2") (pintype "passive"))
    )
    (net (code "90") (name "Net-(U4-SW1)") (class "Default")
      (node (ref "L1") (pin "1") (pinfunction "1_1") (pintype "passive"))
      (node (ref "U4") (pin "11") (pinfunction "SW1_11") (pintype "passive"))
    )
    (net (code "91") (name "Net-(U4-SW2)") (class "Default")
      (node (ref "L3") (pin "1") (pinfunction "1_1") (pintype "passive"))
      (node (ref "U4") (pin "6") (pinfunction "SW2_6") (pintype "passive"))
    )
    (net (code "92") (name "Net-(U4-SW3)") (class "Default")
      (node (ref "L2") (pin "1") (pinfunction "1_1") (pintype "passive"))
      (node (ref "U4") (pin "20") (pinfunction "SW3_20") (pintype "passive"))
    )
    (net (code "93") (name "Net-(U5-EN)") (class "Default")
      (node (ref "R32") (pin "1") (pinfunction "1_1") (pintype "passive"))
      (node (ref "R35") (pin "1") (pinfunction "1_1") (pintype "passive"))
      (node (ref "R36") (pin "2") (pinfunction "2_2") (pintype "passive"))
      (node (ref "U5") (pin "4") (pinfunction "EN_4") (pintype "passive"))
    )
    (net (code "94") (name "Net-(U5-SW)") (class "Default")
      (node (ref "D1") (pin "A") (pinfunction "A_A") (pintype "passive"))
      (node (ref "L4") (pin "2") (pinfunction "2_2") (pintype "passive"))
      (node (ref "U5") (pin "1") (pinfunction "SW_1") (pintype "passive"))
    )
    (net (code "95") (name "Net-(U6-PENIRQ)") (class "Default")
      (node (ref "D4") (pin "K") (pinfunction "K_K") (pintype "passive"))
      (node (ref "U6") (pin "7") (pinfunction "PENIRQ_7") (pintype "passive"))
    )
    (net (code "96") (name "Net-(U7-RXD)") (class "Default")
      (node (ref "R42") (pin "2") (pinfunction "2_2") (pintype "passive"))
      (node (ref "R43") (pin "2") (pinfunction "2_2") (pintype "passive"))
      (node (ref "U7") (pin "20") (pinfunction "RXD_20") (pintype "passive"))
    )
    (net (code "97") (name "Net-(U7-TXD)") (class "Default")
      (node (ref "R39") (pin "2") (pinfunction "2_2") (pintype "passive"))
      (node (ref "R40") (pin "2") (pinfunction "2_2") (pintype "passive"))
      (node (ref "U7") (pin "21") (pinfunction "TXD_21") (pintype "passive"))
    )
    (net (code "98") (name "Net-(U7-VDD)") (class "Default")
      (node (ref "C42") (pin "1") (pinfunction "1_1") (pintype "passive"))
      (node (ref "R25") (pin "1") (pinfunction "1_1") (pintype "passive"))
      (node (ref "U7") (pin "5") (pinfunction "VIO_5") (pintype "passive"))
      (node (ref "U7") (pin "6") (pinfunction "VDD_6") (pintype "passive"))
    )
    (net (code "99") (name "Net-(U7-~{RS}T)") (class "Default")
      (node (ref "R25") (pin "2") (pinfunction "2_2") (pintype "passive"))
      (node (ref "U7") (pin "9") (pinfunction "~{RS}T_9") (pintype "passive"))
    )
    (net (code "100") (name "Net-(U8-Y0)") (class "Default")
      (node (ref "R38") (pin "1") (pinfunction "1_1") (pintype "passive"))
      (node (ref "U8") (pin "24") (pinfunction "Y0_24") (pintype "passive"))
    )
    (net (code "101") (name "Net-(U8-Y1)") (class "Default")
      (node (ref "R41") (pin "1") (pinfunction "1_1") (pintype "passive"))
      (node (ref "U8") (pin "23") (pinfunction "Y1_23") (pintype "passive"))
    )
    (net (code "102") (name "Net-(U11-IN)") (class "Default")
      (node (ref "C54") (pin "2") (pinfunction "2_2") (pintype "passive"))
      (node (ref "U11") (pin "3") (pinfunction "IN_3") (pintype "passive"))
    )
    (net (code "103") (name "Net-(U11-VDD)") (class "Default")
      (node (ref "C47") (pin "1") (pinfunction "1_1") (pintype "passive"))
      (node (ref "R46") (pin "2") (pinfunction "2_2") (pintype "passive"))
      (node (ref "U11") (pin "4") (pinfunction "~{SD}_4") (pintype "passive"))
      (node (ref "U11") (pin "5") (pinfunction "VDD_5") (pintype "passive"))
    )
    (net (code "104") (name "VCC3V3") (class "Default")
      (node (ref "C28") (pin "1") (pinfunction "1_1") (pintype "passive"))
      (node (ref "C29") (pin "2") (pinfunction "2_2") (pintype "passive"))
      (node (ref "C41") (pin "1") (pinfunction "1_1") (pintype "passive"))
      (node (ref "C51") (pin "2") (pinfunction "2_2") (pintype "passive"))
      (node (ref "C52") (pin "1") (pinfunction "1_1") (pintype "passive"))
      (node (ref "C59") (pin "1") (pinfunction "1_1") (pintype "passive"))
      (node (ref "C60") (pin "2") (pinfunction "2_2") (pintype "passive"))
      (node (ref "DS1") (pin "A") (pinfunction "1_A") (pintype "passive"))
      (node (ref "J1") (pin "4") (pinfunction "VDD_4") (pintype "power_in"))
      (node (ref "L1") (pin "2") (pinfunction "2_2") (pintype "passive"))
      (node (ref "P1") (pin "31") (pinfunction "DISP_31") (pintype "passive"))
      (node (ref "P1") (pin "4") (pinfunction "VDD_4") (pintype "passive"))
      (node (ref "P2") (pin "6") (pinfunction "6_6") (pintype "passive"))
      (node (ref "P4") (pin "2") (pinfunction "2_2") (pintype "passive"))
      (node (ref "R16") (pin "1") (pinfunction "1_1") (pintype "passive"))
      (node (ref "R17") (pin "1") (pinfunction "1_1") (pintype "passive"))
      (node (ref "R18") (pin "1") (pinfunction "1_1") (pintype "passive"))
      (node (ref "R19") (pin "1") (pinfunction "1_1") (pintype "passive"))
      (node (ref "R20") (pin "1") (pinfunction "1_1") (pintype "passive"))
      (node (ref "R21") (pin "2") (pinfunction "2_2") (pintype "passive"))
      (node (ref "R22") (pin "2") (pinfunction "2_2") (pintype "passive"))
      (node (ref "R31") (pin "1") (pinfunction "1_1") (pintype "passive"))
      (node (ref "R33") (pin "2") (pinfunction "2_2") (pintype "passive"))
      (node (ref "R36") (pin "1") (pinfunction "1_1") (pintype "passive"))
      (node (ref "R41") (pin "2") (pinfunction "2_2") (pintype "passive"))
      (node (ref "R8") (pin "1") (pinfunction "1_1") (pintype "passive"))
      (node (ref "U10") (pin "3") (pinfunction "IN_3") (pintype "passive"))
      (node (ref "U2") (pin "3") (pinfunction "IN_3") (pintype "passive"))
      (node (ref "U6") (pin "1") (pinfunction "VCC_1") (pintype "passive"))
      (node (ref "U9") (pin "3") (pinfunction "IN_3") (pintype "passive"))
    )
    (net (code "105") (name "VCCIN") (class "Default")
      (node (ref "C25") (pin "1") (pinfunction "1_1") (pintype "passive"))
      (node (ref "C26") (pin "1") (pinfunction "1_1") (pintype "passive"))
      (node (ref "C27") (pin "1") (pinfunction "1_1") (pintype "passive"))
      (node (ref "C43") (pin "2") (pinfunction "2_2") (pintype "passive"))
      (node (ref "F1") (pin "2") (pinfunction "2_2") (pintype "passive"))
      (node (ref "J2") (pin "1") (pinfunction "VBUS_1") (pintype "power_in"))
      (node (ref "J3") (pin "1") (pinfunction "VBUS_1") (pintype "power_in"))
      (node (ref "P2") (pin "1") (pinfunction "1_1") (pintype "passive"))
      (node (ref "U4") (pin "10") (pinfunction "VIN1_10") (pintype "passive"))
      (node (ref "U4") (pin "16") (pinfunction "VCC_16") (pintype "passive"))
      (node (ref "U4") (pin "18") (pinfunction "EN3_18") (pintype "passive"))
      (node (ref "U4") (pin "19") (pinfunction "VIN3_19") (pintype "passive"))
      (node (ref "U4") (pin "7") (pinfunction "VIN2_7") (pintype "passive"))
      (node (ref "U4") (pin "8") (pinfunction "EN2_8") (pintype "passive"))
      (node (ref "U4") (pin "9") (pinfunction "EN1_9") (pintype "passive"))
      (node (ref "U7") (pin "7") (pinfunction "REGIN_7") (pintype "passive"))
      (node (ref "U7") (pin "8") (pinfunction "VBUS_8") (pintype "power_in"))
    )
    (net (code "106") (name "VCC_CORE") (class "Default")
      (node (ref "C32") (pin "1") (pinfunction "1_1") (pintype "passive"))
      (node (ref "C33") (pin "2") (pinfunction "2_2") (pintype "passive"))
      (node (ref "L2") (pin "2") (pinfunction "2_2") (pintype "passive"))
      (node (ref "R12") (pin "1") (pinfunction "1_1") (pintype "passive"))
      (node (ref "R24") (pin "2") (pinfunction "2_2") (pintype "passive"))
    )
    (net (code "107") (name "VCC_DRAM") (class "Default")
      (node (ref "C30") (pin "1") (pinfunction "1_1") (pintype "passive"))
      (node (ref "C31") (pin "2") (pinfunction "2_2") (pintype "passive"))
      (node (ref "L3") (pin "2") (pinfunction "2_2") (pintype "passive"))
      (node (ref "R10") (pin "1") (pinfunction "1_1") (pintype "passive"))
    )
    (net (code "108") (name "unconnected-(J2-ID-Pad4)") (class "Default")
      (node (ref "J2") (pin "4") (pinfunction "ID_4") (pintype "passive+no_connect"))
    )
    (net (code "109") (name "unconnected-(J3-ID-Pad4)") (class "Default")
      (node (ref "J3") (pin "4") (pinfunction "ID_4") (pintype "passive"))
    )
    (net (code "110") (name "unconnected-(P3-Pad5)") (class "Default")
      (node (ref "P3") (pin "5") (pinfunction "5_5") (pintype "passive+no_connect"))
    )
    (net (code "111") (name "unconnected-(P3-Pad6)") (class "Default")
      (node (ref "P3") (pin "6") (pinfunction "6_6") (pintype "passive+no_connect"))
    )
    (net (code "112") (name "unconnected-(P3-Pad7)") (class "Default")
      (node (ref "P3") (pin "7") (pinfunction "7_7") (pintype "passive+no_connect"))
    )
    (net (code "113") (name "unconnected-(P3-Pad8)") (class "Default")
      (node (ref "P3") (pin "8") (pinfunction "8_8") (pintype "passive+no_connect"))
    )
    (net (code "114") (name "unconnected-(P3-Pad9)") (class "Default")
      (node (ref "P3") (pin "9") (pinfunction "9_9") (pintype "passive+no_connect"))
    )
    (net (code "115") (name "unconnected-(P3-Pad10)") (class "Default")
      (node (ref "P3") (pin "10") (pinfunction "10_10") (pintype "passive+no_connect"))
    )
    (net (code "116") (name "unconnected-(U7-CTS-Pad18)") (class "Default")
      (node (ref "U7") (pin "18") (pinfunction "CTS_18") (pintype "passive+no_connect"))
    )
    (net (code "117") (name "unconnected-(U7-DCD-Pad24)") (class "Default")
      (node (ref "U7") (pin "24") (pinfunction "DCD_24") (pintype "passive+no_connect"))
    )
    (net (code "118") (name "unconnected-(U7-DSR-Pad22)") (class "Default")
      (node (ref "U7") (pin "22") (pinfunction "DSR_22") (pintype "passive+no_connect"))
    )
    (net (code "119") (name "unconnected-(U7-DTR-Pad23)") (class "Default")
      (node (ref "U7") (pin "23") (pinfunction "DTR_23") (pintype "passive+no_connect"))
    )
    (net (code "120") (name "unconnected-(U7-GPIO.0-Pad14)") (class "Default")
      (node (ref "U7") (pin "14") (pinfunction "GPIO.0_14") (pintype "passive+no_connect"))
    )
    (net (code "121") (name "unconnected-(U7-GPIO.1-Pad13)") (class "Default")
      (node (ref "U7") (pin "13") (pinfunction "GPIO.1_13") (pintype "passive+no_connect"))
    )
    (net (code "122") (name "unconnected-(U7-GPIO.2-Pad12)") (class "Default")
      (node (ref "U7") (pin "12") (pinfunction "GPIO.2_12") (pintype "passive+no_connect"))
    )
    (net (code "123") (name "unconnected-(U7-GPIO.3-Pad11)") (class "Default")
      (node (ref "U7") (pin "11") (pinfunction "GPIO.3_11") (pintype "passive+no_connect"))
    )
    (net (code "124") (name "unconnected-(U7-NC-Pad10)") (class "Default")
      (node (ref "U7") (pin "10") (pinfunction "NC_10") (pintype "passive+no_connect"))
    )
    (net (code "125") (name "unconnected-(U7-RI-Pad1)") (class "Default")
      (node (ref "U7") (pin "1") (pinfunction "RI_1") (pintype "passive+no_connect"))
    )
    (net (code "126") (name "unconnected-(U7-RTS-Pad19)") (class "Default")
      (node (ref "U7") (pin "19") (pinfunction "RTS_19") (pintype "passive+no_connect"))
    )
    (net (code "127") (name "unconnected-(U7-SUSPEND-Pad17)") (class "Default")
      (node (ref "U7") (pin "17") (pinfunction "SUSPEND_17") (pintype "passive+no_connect"))
    )
    (net (code "128") (name "unconnected-(U7-VPP-Pad16)") (class "Default")
      (node (ref "U7") (pin "16") (pinfunction "VPP_16") (pintype "passive+no_connect"))
    )
    (net (code "129") (name "unconnected-(U7-~{SUSPEND}-Pad15)") (class "Default")
      (node (ref "U7") (pin "15") (pinfunction "~{SUSPEND}_15") (pintype "passive+no_connect"))
    )
    (net (code "130") (name "unconnected-(U8-STROBE-Pad1)") (class "Default")
      (node (ref "U8") (pin "1") (pinfunction "STROBE_1") (pintype "passive+no_connect"))
    )
  )
)
